# Qwiic_UV_Sensor_VEML6075.net
KiCad netlist of a schematic drawn in EAGLE
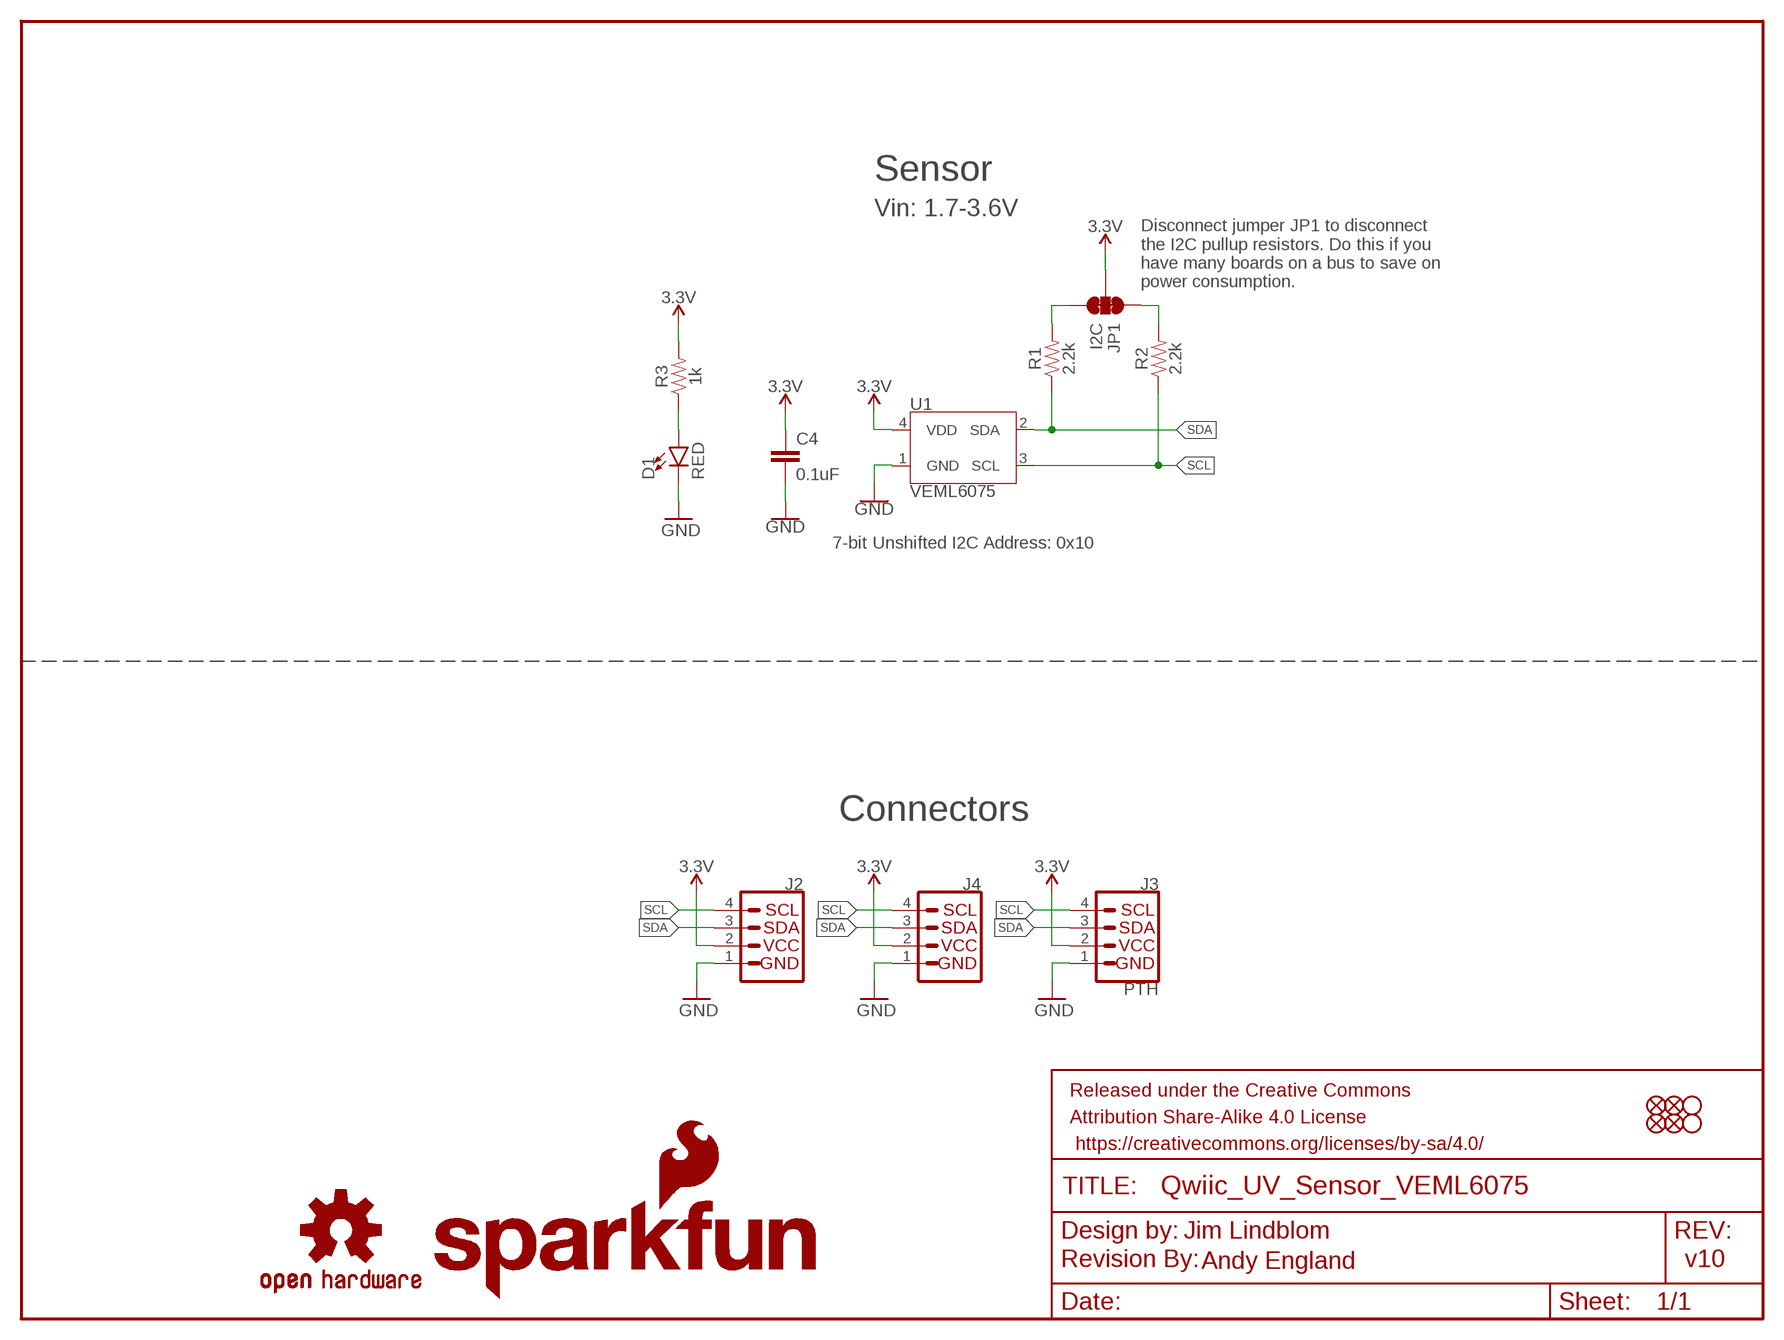
[diagram p0: schematic, sheet 1]

(export (version "E")
  (design (tool "Eeschema 10.0.6"))
  (components
    (comp (ref "C4")
      (value "0.1uF")
      (footprint "eagle-import:0603")
      (libsource (lib "eagle-import") (part "0.1UF-0603-25V-(+80/-20%)"))
    )
    (comp (ref "D1")
      (value "RED")
      (footprint "eagle-import:LED-0603")
      (libsource (lib "eagle-import") (part "LED-RED0603"))
    )
    (comp (ref "FRAME1")
      (value "FRAME-LETTER")
      (footprint "eagle-import:CREATIVE_COMMONS")
      (libsource (lib "eagle-import") (part "FRAME-LETTER"))
    )
    (comp (ref "J2")
      (value "QWIIC_CONNECTORJS-1MM")
      (footprint "eagle-import:1X04_1MM_RA")
      (libsource (lib "eagle-import") (part "QWIIC_CONNECTORJS-1MM"))
    )
    (comp (ref "J3")
      (value "PTH")
      (footprint "eagle-import:1X04_NO_SILK")
      (libsource (lib "eagle-import") (part "I2C_STANDARD_NO_SILK"))
    )
    (comp (ref "J4")
      (value "QWIIC_CONNECTORJS-1MM")
      (footprint "eagle-import:1X04_1MM_RA")
      (libsource (lib "eagle-import") (part "QWIIC_CONNECTORJS-1MM"))
    )
    (comp (ref "JP1")
      (value "I2C")
      (footprint "eagle-import:SMT-JUMPER_3_2-NC_TRACE_SILK")
      (libsource (lib "eagle-import") (part "JUMPER-SMT_3_2-NC_TRACE_SILK"))
    )
    (comp (ref "JP2")
      (value "FIDUCIALUFIDUCIAL")
      (footprint "eagle-import:MICRO-FIDUCIAL")
      (libsource (lib "eagle-import") (part "FIDUCIALUFIDUCIAL"))
    )
    (comp (ref "JP3")
      (value "STAND-OFF")
      (footprint "eagle-import:STAND-OFF")
      (libsource (lib "eagle-import") (part "STAND-OFF"))
    )
    (comp (ref "JP4")
      (value "STAND-OFF")
      (footprint "eagle-import:STAND-OFF")
      (libsource (lib "eagle-import") (part "STAND-OFF"))
    )
    (comp (ref "JP5")
      (value "FIDUCIALUFIDUCIAL")
      (footprint "eagle-import:MICRO-FIDUCIAL")
      (libsource (lib "eagle-import") (part "FIDUCIALUFIDUCIAL"))
    )
    (comp (ref "JP6")
      (value "FIDUCIALUFIDUCIAL")
      (footprint "eagle-import:MICRO-FIDUCIAL")
      (libsource (lib "eagle-import") (part "FIDUCIALUFIDUCIAL"))
    )
    (comp (ref "JP7")
      (value "FIDUCIALUFIDUCIAL")
      (footprint "eagle-import:MICRO-FIDUCIAL")
      (libsource (lib "eagle-import") (part "FIDUCIALUFIDUCIAL"))
    )
    (comp (ref "LOGO1")
      (value "OSHW-LOGOMINI")
      (footprint "eagle-import:OSHW-LOGO-MINI")
      (libsource (lib "eagle-import") (part "OSHW-LOGOMINI"))
    )
    (comp (ref "LOGO2")
      (value "REVISION")
      (footprint "eagle-import:REVISION")
      (libsource (lib "eagle-import") (part "REVISION"))
    )
    (comp (ref "R1")
      (value "2.2k")
      (footprint "eagle-import:0603")
      (libsource (lib "eagle-import") (part "2.2KOHM-0603-1/10W-1%"))
    )
    (comp (ref "R2")
      (value "2.2k")
      (footprint "eagle-import:0603")
      (libsource (lib "eagle-import") (part "2.2KOHM-0603-1/10W-1%"))
    )
    (comp (ref "R3")
      (value "1k")
      (footprint "eagle-import:0603")
      (libsource (lib "eagle-import") (part "1KOHM-0603-1/10W-1%"))
    )
    (comp (ref "U$1")
      (value "SFE_LOGO_NAME_FLAME.1_INCH")
      (footprint "eagle-import:SFE_LOGO_NAME_FLAME_.1")
      (libsource (lib "eagle-import") (part "SFE_LOGO_NAME_FLAME.1_INCH"))
    )
    (comp (ref "U$2")
      (value "SFE_LOGO_NAME_FLAME.1_INCH")
      (footprint "eagle-import:SFE_LOGO_NAME_FLAME_.1")
      (libsource (lib "eagle-import") (part "SFE_LOGO_NAME_FLAME.1_INCH"))
    )
    (comp (ref "U1")
      (value "VEML6075")
      (footprint "eagle-import:VEML6075_A3OP")
      (libsource (lib "eagle-import") (part "VEML6075"))
    )
  )
  (nets
    (net (code "1") (name "3.3V") (class "Default")
      (node (ref "C4") (pin "1") (pinfunction "1_1") (pintype "passive"))
      (node (ref "J2") (pin "2") (pinfunction "2_2") (pintype "power_in"))
      (node (ref "J3") (pin "2") (pinfunction "VCC_2") (pintype "power_in"))
      (node (ref "J4") (pin "2") (pinfunction "2_2") (pintype "power_in"))
      (node (ref "JP1") (pin "2") (pinfunction "2_2") (pintype "passive"))
      (node (ref "R3") (pin "2") (pinfunction "2_2") (pintype "passive"))
      (node (ref "U1") (pin "4") (pinfunction "VDD_4") (pintype "bidirectional"))
    )
    (net (code "2") (name "GND") (class "Default")
      (node (ref "C4") (pin "2") (pinfunction "2_2") (pintype "passive"))
      (node (ref "D1") (pin "C") (pinfunction "C_C") (pintype "passive"))
      (node (ref "J2") (pin "1") (pinfunction "1_1") (pintype "power_in"))
      (node (ref "J3") (pin "1") (pinfunction "GND_1") (pintype "power_in"))
      (node (ref "J4") (pin "1") (pinfunction "1_1") (pintype "power_in"))
      (node (ref "U1") (pin "1") (pinfunction "GND_1") (pintype "bidirectional"))
    )
    (net (code "3") (name "Net-(D1-PadA)") (class "Default")
      (node (ref "D1") (pin "A") (pinfunction "A_A") (pintype "passive"))
      (node (ref "R3") (pin "1") (pinfunction "1_1") (pintype "passive"))
    )
    (net (code "4") (name "Net-(JP1-Pad1)") (class "Default")
      (node (ref "JP1") (pin "1") (pinfunction "1_1") (pintype "passive"))
      (node (ref "R2") (pin "2") (pinfunction "2_2") (pintype "passive"))
    )
    (net (code "5") (name "Net-(JP1-Pad3)") (class "Default")
      (node (ref "JP1") (pin "3") (pinfunction "3_3") (pintype "passive"))
      (node (ref "R1") (pin "2") (pinfunction "2_2") (pintype "passive"))
    )
    (net (code "6") (name "SCL") (class "Default")
      (node (ref "J2") (pin "4") (pinfunction "4_4") (pintype "passive"))
      (node (ref "J3") (pin "4") (pinfunction "SCL_4") (pintype "passive"))
      (node (ref "J4") (pin "4") (pinfunction "4_4") (pintype "passive"))
      (node (ref "R2") (pin "1") (pinfunction "1_1") (pintype "passive"))
      (node (ref "U1") (pin "3") (pinfunction "SCL_3") (pintype "bidirectional"))
    )
    (net (code "7") (name "SDA") (class "Default")
      (node (ref "J2") (pin "3") (pinfunction "3_3") (pintype "passive"))
      (node (ref "J3") (pin "3") (pinfunction "SDA_3") (pintype "passive"))
      (node (ref "J4") (pin "3") (pinfunction "3_3") (pintype "passive"))
      (node (ref "R1") (pin "1") (pinfunction "1_1") (pintype "passive"))
      (node (ref "U1") (pin "2") (pinfunction "SDA_2") (pintype "bidirectional"))
    )
  )
)
